# esp12power_supply_ceramic.net
KiCad netlist of a schematic drawn in EAGLE
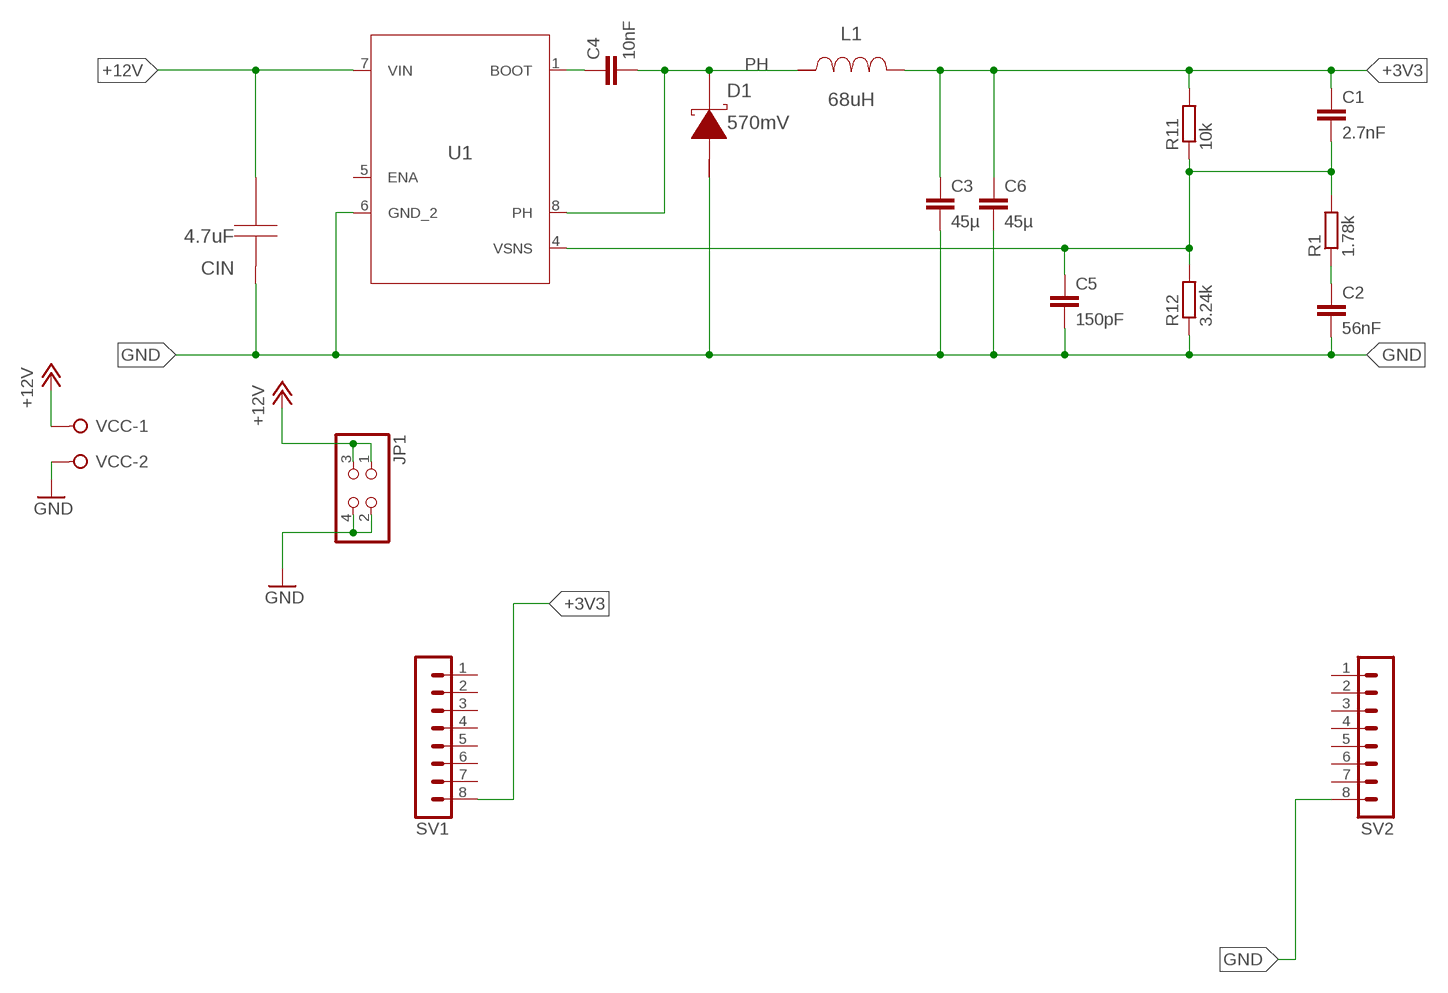
[diagram p0: schematic, sheet 1]

(export (version "E")
  (design (tool "Eeschema 10.0.6"))
  (components
    (comp (ref "C1")
      (value "2.7nF")
      (footprint "eagle-import:C0805K")
      (libsource (lib "eagle-import") (part "C-EUC0805K"))
    )
    (comp (ref "C2")
      (value "56nF")
      (footprint "eagle-import:C0805K")
      (libsource (lib "eagle-import") (part "C-EUC0805K"))
    )
    (comp (ref "C3")
      (value "45µ")
      (footprint "eagle-import:C1210K")
      (libsource (lib "eagle-import") (part "C-EUC1210K"))
    )
    (comp (ref "C4")
      (value "10nF")
      (footprint "eagle-import:C0805")
      (libsource (lib "eagle-import") (part "resistor_C-EUC0805"))
    )
    (comp (ref "C5")
      (value "150pF")
      (footprint "eagle-import:C0805K")
      (libsource (lib "eagle-import") (part "C-EUC0805K"))
    )
    (comp (ref "C6")
      (value "45µ")
      (footprint "eagle-import:C1210K")
      (libsource (lib "eagle-import") (part "C-EUC1210K"))
    )
    (comp (ref "CIN")
      (value "4.7uF")
      (footprint "eagle-import:1206")
      (fields (field (name "MANUFACTURER_PART_NUMBER") "GRM31CR71H475KA12L"))
      (libsource (lib "eagle-import") (part "GRM31CR71H475KA12L"))
    )
    (comp (ref "D1")
      (value "570mV")
      (footprint "eagle-import:SMA")
      (fields (field (name "MANUFACTURER_PART_NUMBER") "B16013F"))
      (libsource (lib "eagle-import") (part "B160-13-F"))
    )
    (comp (ref "JP1")
      (value "PINHD-2X2")
      (footprint "eagle-import:2X02")
      (libsource (lib "eagle-import") (part "PINHD-2X2"))
    )
    (comp (ref "L1")
      (value "68uH")
      (footprint "eagle-import:IND_NPI75C")
      (fields (field (name "MANUFACTURER_PART_NUMBER") "NPI75C560KTRF"))
      (libsource (lib "eagle-import") (part "NPI75C560KTRF"))
    )
    (comp (ref "R1")
      (value "1.78k")
      (footprint "eagle-import:R0805")
      (libsource (lib "eagle-import") (part "R-EU_R0805"))
    )
    (comp (ref "R11")
      (value "10k")
      (footprint "eagle-import:R0805")
      (libsource (lib "eagle-import") (part "R-EU_R0805"))
    )
    (comp (ref "R12")
      (value "3.24k")
      (footprint "eagle-import:R0805")
      (libsource (lib "eagle-import") (part "R-EU_R0805"))
    )
    (comp (ref "SV1")
      (value "MA08-1")
      (footprint "eagle-import:MA08-1")
      (libsource (lib "eagle-import") (part "MA08-1"))
    )
    (comp (ref "SV2")
      (value "MA08-1")
      (footprint "eagle-import:MA08-1")
      (libsource (lib "eagle-import") (part "MA08-1"))
    )
    (comp (ref "U1")
      (value "TPS5410DR")
      (footprint "eagle-import:M08A")
      (libsource (lib "eagle-import") (part "TPS5410DR"))
    )
    (comp (ref "VCC")
      (value "W237-02P")
      (footprint "eagle-import:W237-132")
      (libsource (lib "eagle-import") (part "W237-02P"))
    )
  )
  (nets
    (net (code "1") (name "+3V3") (class "Default")
      (node (ref "C1") (pin "1") (pinfunction "1_1") (pintype "passive"))
      (node (ref "C3") (pin "1") (pinfunction "1_1") (pintype "passive"))
      (node (ref "C6") (pin "1") (pinfunction "1_1") (pintype "passive"))
      (node (ref "L1") (pin "1") (pinfunction "1_1") (pintype "passive"))
      (node (ref "R11") (pin "2") (pinfunction "2_2") (pintype "passive"))
      (node (ref "SV1") (pin "8") (pinfunction "8_8") (pintype "passive"))
    )
    (net (code "2") (name "+12V") (class "Default")
      (node (ref "CIN") (pin "2") (pinfunction "2_2") (pintype "passive"))
      (node (ref "JP1") (pin "1") (pinfunction "1_1") (pintype "passive"))
      (node (ref "JP1") (pin "3") (pinfunction "3_3") (pintype "passive"))
      (node (ref "U1") (pin "7") (pinfunction "VIN_7") (pintype "passive"))
      (node (ref "VCC") (pin "1") (pinfunction "KL_1") (pintype "passive"))
    )
    (net (code "3") (name "/PH") (class "Default")
      (node (ref "C4") (pin "2") (pinfunction "2_2") (pintype "passive"))
      (node (ref "D1") (pin "1") (pinfunction "K_1") (pintype "passive"))
      (node (ref "L1") (pin "2") (pinfunction "2_2") (pintype "passive"))
      (node (ref "U1") (pin "8") (pinfunction "PH_8") (pintype "passive"))
    )
    (net (code "4") (name "GND") (class "Default")
      (node (ref "C2") (pin "2") (pinfunction "2_2") (pintype "passive"))
      (node (ref "C3") (pin "2") (pinfunction "2_2") (pintype "passive"))
      (node (ref "C5") (pin "2") (pinfunction "2_2") (pintype "passive"))
      (node (ref "C6") (pin "2") (pinfunction "2_2") (pintype "passive"))
      (node (ref "CIN") (pin "1") (pinfunction "1_1") (pintype "passive"))
      (node (ref "D1") (pin "2") (pinfunction "A_2") (pintype "passive"))
      (node (ref "JP1") (pin "2") (pinfunction "2_2") (pintype "passive"))
      (node (ref "JP1") (pin "4") (pinfunction "4_4") (pintype "passive"))
      (node (ref "R12") (pin "1") (pinfunction "1_1") (pintype "passive"))
      (node (ref "SV2") (pin "8") (pinfunction "8_8") (pintype "passive"))
      (node (ref "U1") (pin "6") (pinfunction "GND_2_6") (pintype "passive"))
      (node (ref "VCC") (pin "2") (pinfunction "KL_2") (pintype "passive"))
    )
    (net (code "5") (name "Net-(C2-Pad1)") (class "Default")
      (node (ref "C2") (pin "1") (pinfunction "1_1") (pintype "passive"))
      (node (ref "R1") (pin "1") (pinfunction "1_1") (pintype "passive"))
    )
    (net (code "6") (name "Net-(U1-BOOT)") (class "Default")
      (node (ref "C4") (pin "1") (pinfunction "1_1") (pintype "passive"))
      (node (ref "U1") (pin "1") (pinfunction "BOOT_1") (pintype "passive"))
    )
    (net (code "7") (name "Net-(U1-VSNS)") (class "Default")
      (node (ref "C1") (pin "2") (pinfunction "2_2") (pintype "passive"))
      (node (ref "C5") (pin "1") (pinfunction "1_1") (pintype "passive"))
      (node (ref "R1") (pin "2") (pinfunction "2_2") (pintype "passive"))
      (node (ref "R11") (pin "1") (pinfunction "1_1") (pintype "passive"))
      (node (ref "R12") (pin "2") (pinfunction "2_2") (pintype "passive"))
      (node (ref "U1") (pin "4") (pinfunction "VSNS_4") (pintype "passive"))
    )
    (net (code "8") (name "unconnected-(SV1-Pad1)") (class "Default")
      (node (ref "SV1") (pin "1") (pinfunction "1_1") (pintype "passive"))
    )
    (net (code "9") (name "unconnected-(SV1-Pad2)") (class "Default")
      (node (ref "SV1") (pin "2") (pinfunction "2_2") (pintype "passive"))
    )
    (net (code "10") (name "unconnected-(SV1-Pad3)") (class "Default")
      (node (ref "SV1") (pin "3") (pinfunction "3_3") (pintype "passive"))
    )
    (net (code "11") (name "unconnected-(SV1-Pad4)") (class "Default")
      (node (ref "SV1") (pin "4") (pinfunction "4_4") (pintype "passive"))
    )
    (net (code "12") (name "unconnected-(SV1-Pad5)") (class "Default")
      (node (ref "SV1") (pin "5") (pinfunction "5_5") (pintype "passive"))
    )
    (net (code "13") (name "unconnected-(SV1-Pad6)") (class "Default")
      (node (ref "SV1") (pin "6") (pinfunction "6_6") (pintype "passive"))
    )
    (net (code "14") (name "unconnected-(SV1-Pad7)") (class "Default")
      (node (ref "SV1") (pin "7") (pinfunction "7_7") (pintype "passive"))
    )
    (net (code "15") (name "unconnected-(SV2-Pad1)") (class "Default")
      (node (ref "SV2") (pin "1") (pinfunction "1_1") (pintype "passive"))
    )
    (net (code "16") (name "unconnected-(SV2-Pad2)") (class "Default")
      (node (ref "SV2") (pin "2") (pinfunction "2_2") (pintype "passive"))
    )
    (net (code "17") (name "unconnected-(SV2-Pad3)") (class "Default")
      (node (ref "SV2") (pin "3") (pinfunction "3_3") (pintype "passive"))
    )
    (net (code "18") (name "unconnected-(SV2-Pad4)") (class "Default")
      (node (ref "SV2") (pin "4") (pinfunction "4_4") (pintype "passive"))
    )
    (net (code "19") (name "unconnected-(SV2-Pad5)") (class "Default")
      (node (ref "SV2") (pin "5") (pinfunction "5_5") (pintype "passive"))
    )
    (net (code "20") (name "unconnected-(SV2-Pad6)") (class "Default")
      (node (ref "SV2") (pin "6") (pinfunction "6_6") (pintype "passive"))
    )
    (net (code "21") (name "unconnected-(SV2-Pad7)") (class "Default")
      (node (ref "SV2") (pin "7") (pinfunction "7_7") (pintype "passive"))
    )
    (net (code "22") (name "unconnected-(U1-ENA-Pad5)") (class "Default")
      (node (ref "U1") (pin "5") (pinfunction "ENA_5") (pintype "passive"))
    )
  )
)
